# v1_1.net
KiCad netlist of a schematic drawn in Altium Designer
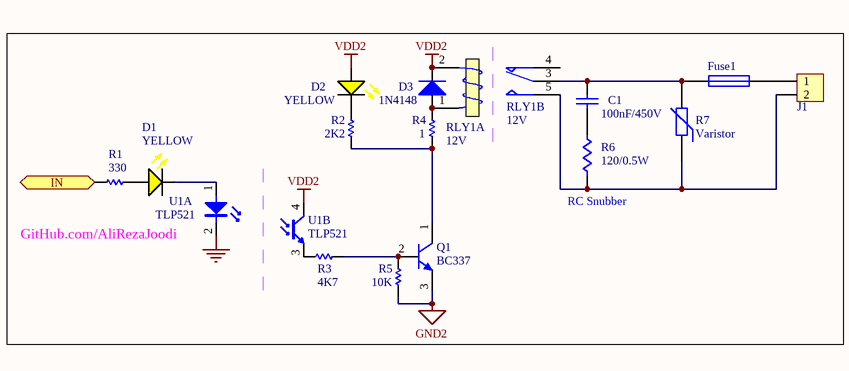
[diagram p0: v1.1.SchDoc]

(export (version "E")
  (design (tool "Eeschema 10.0.6"))
  (components
    (comp (ref "C1")
      (value "100nF/450V")
      (footprint "C_THD_CER_(P2.54-D3.5-T1.5)")
      (description "Capacitor, Ceramic Multilayer")
      (libsource (lib "Passive") (part "Capacitor_Ceramic"))
    )
    (comp (ref "D1")
      (value "YELLOW")
      (footprint "LED_THD_5MM_YELLOW")
      (description "LED, Yellow")
      (fields (field (name "MANUFACTURER") "Generic Components") (field (name "PUBLISHER") "Altium Limited"))
      (libsource (lib "Display") (part "LED_YELLOW"))
    )
    (comp (ref "D2")
      (value "YELLOW")
      (footprint "LED_THD_5MM_YELLOW")
      (description "LED, Yellow")
      (fields (field (name "MANUFACTURER") "Generic Components") (field (name "PUBLISHER") "Altium Limited"))
      (libsource (lib "Display") (part "LED_YELLOW"))
    )
    (comp (ref "D3")
      (value "1N4148")
      (footprint "DIODE0.4_Glass")
      (description "Default Diode")
      (fields (field (name "MANUFACTURER") "Generic Components") (field (name "PUBLISHER") "Altium Limited"))
      (libsource (lib "Miscellaneous Devices") (part "Diode"))
    )
    (comp (ref "Fuse1")
      (value "2A")
      (footprint "PIN-W2/E2.8")
      (description "Fuse")
      (fields (field (name "MANUFACTURER") "Generic Components") (field (name "PUBLISHER") "Altium Limited"))
      (libsource (lib "Miscellaneous Devices") (part "Fuse 1"))
    )
    (comp (ref "J1")
      (value "2PIN")
      (footprint "Connector_Phoenix_2PIN_MSTB")
      (description "Connector, Header, 2Pin")
      (libsource (lib "Connector") (part "Connector_Header_2Pin"))
    )
    (comp (ref "Q1")
      (value "BC337")
      (footprint "TO92C")
      (description "NPN Bipolar Transistor")
      (fields (field (name "MANUFACTURER") "Generic Components") (field (name "PUBLISHER") "Altium Limited"))
      (libsource (lib "Miscellaneous Devices") (part "NPN"))
    )
    (comp (ref "R1")
      (value "330")
      (footprint "R_THD_AXIAL0.4(1/4W)")
      (description "Resistor")
      (libsource (lib "Passive") (part "Resistor"))
    )
    (comp (ref "R2")
      (value "2K2")
      (footprint "R_THD_AXIAL0.4(1/4W)")
      (description "Resistor")
      (libsource (lib "Passive") (part "Resistor"))
    )
    (comp (ref "R3")
      (value "4K7")
      (footprint "R_THD_AXIAL0.4(1/4W)")
      (description "Resistor")
      (libsource (lib "Passive") (part "Resistor"))
    )
    (comp (ref "R4")
      (value "1")
      (footprint "R_THD_AXIAL0.4(1/4W)")
      (description "Resistor")
      (libsource (lib "Passive") (part "Resistor"))
    )
    (comp (ref "R5")
      (value "10K")
      (footprint "R_THD_AXIAL0.4(1/4W)")
      (description "Resistor")
      (libsource (lib "Passive") (part "Resistor"))
    )
    (comp (ref "R6")
      (value "120/0.5W")
      (footprint "R_THD_AXIAL0.4(1/4W)")
      (description "Resistor")
      (libsource (lib "Passive") (part "Resistor_3Form"))
    )
    (comp (ref "R7")
      (value "Varistor")
      (footprint "R2012-0805")
      (description "Varistor (Voltage-Sensitive Resistor)")
      (fields (field (name "MANUFACTURER") "Generic Components") (field (name "PUBLISHER") "Altium Limited"))
      (libsource (lib "Miscellaneous Devices") (part "Res Varistor"))
    )
    (comp (ref "RLY1")
      (value "12V")
      (footprint "RELAY_SPDT_5PIN_2216")
      (description "SPDT Relay")
      (libsource (lib "Passive") (part "Relay_SPDT_2Form"))
    )
    (comp (ref "U1")
      (value "TLP521")
      (footprint "DIP_4")
      (description "Optoisolator")
      (fields (field (name "PUBLISHER") "Altium Limited"))
      (libsource (lib "Other_Myself") (part "Optoisolator"))
    )
  )
  (nets
    (net (code "1") (name "/IN") (class "Default")
      (node (ref "R1") (pin "2") (pinfunction "2_2") (pintype "passive"))
    )
    (net (code "2") (name "GND") (class "Default")
      (node (ref "U1") (pin "2") (pinfunction "K_2") (pintype "power_in"))
    )
    (net (code "3") (name "GND2") (class "Default")
      (node (ref "Q1") (pin "3") (pinfunction "E_3") (pintype "passive"))
      (node (ref "R5") (pin "2") (pinfunction "2_2") (pintype "passive"))
    )
    (net (code "4") (name "Net-(C1-Pad1)") (class "Default")
      (node (ref "C1") (pin "1") (pinfunction "1_1") (pintype "passive"))
      (node (ref "R6") (pin "2") (pinfunction "2_2") (pintype "passive"))
    )
    (net (code "5") (name "Net-(D1-A)") (class "Default")
      (node (ref "D1") (pin "1") (pinfunction "A_1") (pintype "passive"))
      (node (ref "R1") (pin "1") (pinfunction "1_1") (pintype "passive"))
    )
    (net (code "6") (name "Net-(D1-K)") (class "Default")
      (node (ref "D1") (pin "2") (pinfunction "K_2") (pintype "passive"))
      (node (ref "U1") (pin "1") (pinfunction "A_1") (pintype "power_in"))
    )
    (net (code "7") (name "Net-(D2-K)") (class "Default")
      (node (ref "D2") (pin "2") (pinfunction "K_2") (pintype "passive"))
      (node (ref "R2") (pin "2") (pinfunction "2_2") (pintype "passive"))
    )
    (net (code "8") (name "Net-(D3-A)") (class "Default")
      (node (ref "D3") (pin "1") (pinfunction "A_1") (pintype "passive"))
      (node (ref "R4") (pin "2") (pinfunction "2_2") (pintype "passive"))
      (node (ref "RLY1") (pin "1") (pinfunction "T2_1") (pintype "passive"))
    )
    (net (code "9") (name "Net-(Fuse1-Pad2)") (class "Default")
      (node (ref "Fuse1") (pin "2") (pinfunction "2_2") (pintype "passive"))
      (node (ref "J1") (pin "1") (pinfunction "1_1") (pintype "passive"))
    )
    (net (code "10") (name "Net-(Q1-B)") (class "Default")
      (node (ref "Q1") (pin "2") (pinfunction "B_2") (pintype "passive"))
      (node (ref "R3") (pin "1") (pinfunction "1_1") (pintype "passive"))
      (node (ref "R5") (pin "1") (pinfunction "1_1") (pintype "passive"))
    )
    (net (code "11") (name "Net-(Q1-C)") (class "Default")
      (node (ref "Q1") (pin "1") (pinfunction "C_1") (pintype "passive"))
      (node (ref "R2") (pin "1") (pinfunction "1_1") (pintype "passive"))
      (node (ref "R4") (pin "1") (pinfunction "1_1") (pintype "passive"))
    )
    (net (code "12") (name "Net-(RLY1B-COM)") (class "Default")
      (node (ref "C1") (pin "2") (pinfunction "2_2") (pintype "passive"))
      (node (ref "Fuse1") (pin "1") (pinfunction "1_1") (pintype "passive"))
      (node (ref "R7") (pin "2") (pinfunction "2_2") (pintype "passive"))
      (node (ref "RLY1") (pin "3") (pinfunction "COM_3") (pintype "passive"))
    )
    (net (code "13") (name "Net-(RLY1B-NO)") (class "Default")
      (node (ref "J1") (pin "2") (pinfunction "2_2") (pintype "passive"))
      (node (ref "R6") (pin "1") (pinfunction "1_1") (pintype "passive"))
      (node (ref "R7") (pin "1") (pinfunction "1_1") (pintype "passive"))
      (node (ref "RLY1") (pin "5") (pinfunction "NO_5") (pintype "passive"))
    )
    (net (code "14") (name "Net-(U1B-E)") (class "Default")
      (node (ref "R3") (pin "2") (pinfunction "2_2") (pintype "passive"))
      (node (ref "U1") (pin "3") (pinfunction "E_3") (pintype "passive"))
    )
    (net (code "15") (name "VDD2") (class "Default")
      (node (ref "D2") (pin "1") (pinfunction "A_1") (pintype "passive"))
      (node (ref "D3") (pin "2") (pinfunction "K_2") (pintype "passive"))
      (node (ref "RLY1") (pin "2") (pinfunction "T1_2") (pintype "passive"))
      (node (ref "U1") (pin "4") (pinfunction "C_4") (pintype "passive"))
    )
    (net (code "16") (name "unconnected-(RLY1B-NC-Pad4)") (class "Default")
      (node (ref "RLY1") (pin "4") (pinfunction "NC_4") (pintype "passive"))
    )
  )
)
